# power2pix_connector.net
KiCad netlist of a schematic drawn in Altium Designer
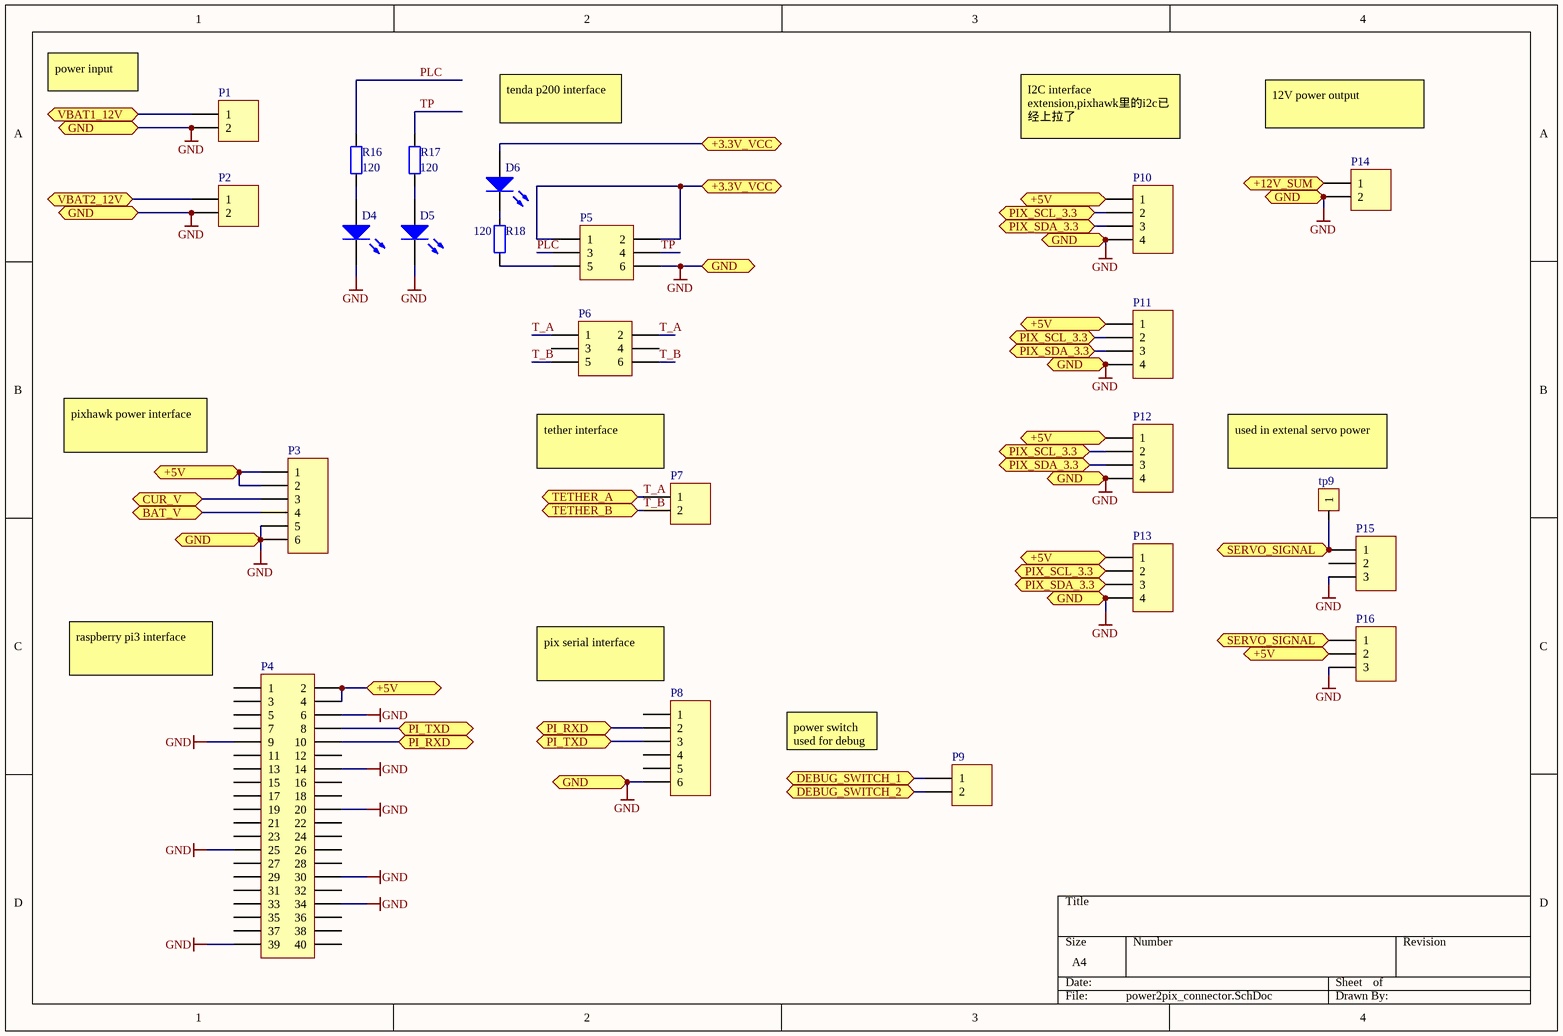
[diagram p0: power2pix_connector.SchDoc]

(export (version "E")
  (design (tool "Eeschema 10.0.6"))
  (components
    (comp (ref "D4")
      (value "LED0")
      (footprint "6-0805_M")
      (description "Typical INFRARED GaAs LED")
      (fields (field (name "PUBLISHER") "Altium Limited"))
      (libsource (lib "Miscellaneous Devices") (part "LED0"))
    )
    (comp (ref "D5")
      (value "LED0")
      (footprint "6-0805_M")
      (description "Typical INFRARED GaAs LED")
      (fields (field (name "PUBLISHER") "Altium Limited"))
      (libsource (lib "Miscellaneous Devices") (part "LED0"))
    )
    (comp (ref "D6")
      (value "LED0")
      (footprint "6-0805_M")
      (description "Typical INFRARED GaAs LED")
      (fields (field (name "PUBLISHER") "Altium Limited"))
      (libsource (lib "Miscellaneous Devices") (part "LED0"))
    )
    (comp (ref "P1")
      (value "Header 2")
      (footprint "M4_POWER")
      (description "Header, 2-Pin")
      (fields (field (name "PUBLISHER") "Altium Limited"))
      (libsource (lib "Miscellaneous Connectors") (part "Header 2"))
    )
    (comp (ref "P2")
      (value "Header 2")
      (footprint "M4_POWER")
      (description "Header, 2-Pin")
      (fields (field (name "PUBLISHER") "Altium Limited"))
      (libsource (lib "Miscellaneous Connectors") (part "Header 2"))
    )
    (comp (ref "P3")
      (value "Header 6")
      (footprint "1.25_6PIN")
      (description "Header, 6-Pin")
      (fields (field (name "PUBLISHER") "Altium Limited"))
      (libsource (lib "Miscellaneous Connectors") (part "Header 6"))
    )
    (comp (ref "P4")
      (value "Header 20X2")
      (footprint "HDR2X20")
      (description "Header, 20-Pin, Dual row")
      (fields (field (name "PUBLISHER") "Altium Limited"))
      (libsource (lib "Miscellaneous Connectors") (part "Header 20X2"))
    )
    (comp (ref "P5")
      (value "Header 3X2")
      (footprint "HDR2X3")
      (description "Header, 3-Pin, Dual row")
      (fields (field (name "PUBLISHER") "Altium Limited"))
      (libsource (lib "Miscellaneous Connectors") (part "Header 3X2"))
    )
    (comp (ref "P6")
      (value "Header 3X2")
      (footprint "HDR2X3")
      (description "Header, 3-Pin, Dual row")
      (fields (field (name "PUBLISHER") "Altium Limited"))
      (libsource (lib "Miscellaneous Connectors") (part "Header 3X2"))
    )
    (comp (ref "P7")
      (value "Header 2")
      (footprint "ConnectorBlue")
      (description "Header, 2-Pin")
      (fields (field (name "PUBLISHER") "Altium Limited"))
      (libsource (lib "Miscellaneous Connectors") (part "Header 2"))
    )
    (comp (ref "P8")
      (value "Header 6")
      (footprint "1.25_6PIN")
      (description "Header, 6-Pin")
      (fields (field (name "PUBLISHER") "Altium Limited"))
      (libsource (lib "Miscellaneous Connectors") (part "Header 6"))
    )
    (comp (ref "P9")
      (value "Header 2")
      (footprint "HDR1X2")
      (description "Header, 2-Pin")
      (fields (field (name "PUBLISHER") "Altium Limited"))
      (libsource (lib "Miscellaneous Connectors") (part "Header 2"))
    )
    (comp (ref "P10")
      (value "Header 4")
      (footprint "1_25_4PIN")
      (description "Header, 4-Pin")
      (fields (field (name "PUBLISHER") "Altium Limited"))
      (libsource (lib "Miscellaneous Connectors") (part "Header 4"))
    )
    (comp (ref "P11")
      (value "Header 4")
      (footprint "HDR1X4")
      (description "Header, 4-Pin")
      (fields (field (name "PUBLISHER") "Altium Limited"))
      (libsource (lib "Miscellaneous Connectors") (part "Header 4"))
    )
    (comp (ref "P12")
      (value "Header 4")
      (footprint "HDR1X4")
      (description "Header, 4-Pin")
      (fields (field (name "PUBLISHER") "Altium Limited"))
      (libsource (lib "Miscellaneous Connectors") (part "Header 4"))
    )
    (comp (ref "P13")
      (value "Header 4")
      (footprint "HDR1X4")
      (description "Header, 4-Pin")
      (fields (field (name "PUBLISHER") "Altium Limited"))
      (libsource (lib "Miscellaneous Connectors") (part "Header 4"))
    )
    (comp (ref "P14")
      (value "Header 2")
      (footprint "M4_POWER")
      (description "Header, 2-Pin")
      (fields (field (name "PUBLISHER") "Altium Limited"))
      (libsource (lib "Miscellaneous Connectors") (part "Header 2"))
    )
    (comp (ref "P15")
      (value "Header 3")
      (footprint "HDR1X3")
      (description "Header, 3-Pin")
      (fields (field (name "PUBLISHER") "Altium Limited"))
      (libsource (lib "Miscellaneous Connectors") (part "Header 3"))
    )
    (comp (ref "P16")
      (value "Header 3")
      (footprint "HDR1X3")
      (description "Header, 3-Pin")
      (fields (field (name "PUBLISHER") "Altium Limited"))
      (libsource (lib "Miscellaneous Connectors") (part "Header 3"))
    )
    (comp (ref "R16")
      (value "120")
      (footprint "6-0805_M")
      (description "Resistor")
      (fields (field (name "Comment") "Res2") (field (name "PUBLISHER") "Altium Limited"))
      (libsource (lib "Miscellaneous Devices") (part "Res2"))
    )
    (comp (ref "R17")
      (value "120")
      (footprint "6-0805_M")
      (description "Resistor")
      (fields (field (name "Comment") "Res2") (field (name "PUBLISHER") "Altium Limited"))
      (libsource (lib "Miscellaneous Devices") (part "Res2"))
    )
    (comp (ref "R18")
      (value "120")
      (footprint "6-0805_M")
      (description "Resistor")
      (fields (field (name "Comment") "Res2") (field (name "PUBLISHER") "Altium Limited"))
      (libsource (lib "Miscellaneous Devices") (part "Res2"))
    )
    (comp (ref "tp9") (value "tp") (footprint "testpoint") (libsource (lib "power2pix_sch_lib") (part "tp")))
  )
  (nets
    (net (code "1") (name "/+3.3V_VCC") (class "Default")
      (node (ref "D6") (pin "1") (pinfunction "A_1") (pintype "passive"))
      (node (ref "P5") (pin "1") (pinfunction "1_1") (pintype "passive"))
      (node (ref "P5") (pin "2") (pinfunction "2_2") (pintype "passive"))
    )
    (net (code "2") (name "/+5V") (class "Default")
      (node (ref "P10") (pin "1") (pinfunction "1_1") (pintype "passive"))
      (node (ref "P11") (pin "1") (pinfunction "1_1") (pintype "passive"))
      (node (ref "P12") (pin "1") (pinfunction "1_1") (pintype "passive"))
      (node (ref "P13") (pin "1") (pinfunction "1_1") (pintype "passive"))
      (node (ref "P16") (pin "2") (pinfunction "2_2") (pintype "passive"))
      (node (ref "P3") (pin "1") (pinfunction "1_1") (pintype "passive"))
      (node (ref "P3") (pin "2") (pinfunction "2_2") (pintype "passive"))
      (node (ref "P4") (pin "2") (pinfunction "2_2") (pintype "passive"))
      (node (ref "P4") (pin "4") (pinfunction "4_4") (pintype "passive"))
    )
    (net (code "3") (name "/+12V_SUM") (class "Default")
      (node (ref "P14") (pin "1") (pinfunction "1_1") (pintype "passive"))
    )
    (net (code "4") (name "/BAT_V") (class "Default")
      (node (ref "P3") (pin "4") (pinfunction "4_4") (pintype "passive"))
    )
    (net (code "5") (name "/CUR_V") (class "Default")
      (node (ref "P3") (pin "3") (pinfunction "3_3") (pintype "passive"))
    )
    (net (code "6") (name "/DEBUG_SWITCH_1") (class "Default")
      (node (ref "P9") (pin "1") (pinfunction "1_1") (pintype "passive"))
    )
    (net (code "7") (name "/DEBUG_SWITCH_2") (class "Default")
      (node (ref "P9") (pin "2") (pinfunction "2_2") (pintype "passive"))
    )
    (net (code "8") (name "/PIX_SCL_3.3") (class "Default")
      (node (ref "P10") (pin "2") (pinfunction "2_2") (pintype "passive"))
      (node (ref "P11") (pin "2") (pinfunction "2_2") (pintype "passive"))
      (node (ref "P12") (pin "2") (pinfunction "2_2") (pintype "passive"))
      (node (ref "P13") (pin "2") (pinfunction "2_2") (pintype "passive"))
    )
    (net (code "9") (name "/PIX_SDA_3.3") (class "Default")
      (node (ref "P10") (pin "3") (pinfunction "3_3") (pintype "passive"))
      (node (ref "P11") (pin "3") (pinfunction "3_3") (pintype "passive"))
      (node (ref "P12") (pin "3") (pinfunction "3_3") (pintype "passive"))
      (node (ref "P13") (pin "3") (pinfunction "3_3") (pintype "passive"))
    )
    (net (code "10") (name "/PI_RXD") (class "Default")
      (node (ref "P4") (pin "10") (pinfunction "10_10") (pintype "passive"))
      (node (ref "P8") (pin "2") (pinfunction "2_2") (pintype "passive"))
    )
    (net (code "11") (name "/PI_TXD") (class "Default")
      (node (ref "P4") (pin "8") (pinfunction "8_8") (pintype "passive"))
      (node (ref "P8") (pin "3") (pinfunction "3_3") (pintype "passive"))
    )
    (net (code "12") (name "/PLC") (class "Default")
      (node (ref "P5") (pin "3") (pinfunction "3_3") (pintype "passive"))
      (node (ref "R16") (pin "2") (pinfunction "2_2") (pintype "passive"))
    )
    (net (code "13") (name "/SERVO_SIGNAL") (class "Default")
      (node (ref "P15") (pin "1") (pinfunction "1_1") (pintype "passive"))
      (node (ref "P16") (pin "1") (pinfunction "1_1") (pintype "passive"))
      (node (ref "tp9") (pin "1") (pinfunction "1_1") (pintype "passive"))
    )
    (net (code "14") (name "/TP") (class "Default")
      (node (ref "P5") (pin "4") (pinfunction "4_4") (pintype "passive"))
      (node (ref "R17") (pin "2") (pinfunction "2_2") (pintype "passive"))
    )
    (net (code "15") (name "/T_A") (class "Default")
      (node (ref "P6") (pin "1") (pinfunction "1_1") (pintype "passive"))
      (node (ref "P6") (pin "2") (pinfunction "2_2") (pintype "passive"))
      (node (ref "P7") (pin "1") (pinfunction "1_1") (pintype "passive"))
    )
    (net (code "16") (name "/T_B") (class "Default")
      (node (ref "P6") (pin "5") (pinfunction "5_5") (pintype "passive"))
      (node (ref "P6") (pin "6") (pinfunction "6_6") (pintype "passive"))
      (node (ref "P7") (pin "2") (pinfunction "2_2") (pintype "passive"))
    )
    (net (code "17") (name "/VBAT1_12V") (class "Default")
      (node (ref "P1") (pin "1") (pinfunction "1_1") (pintype "passive"))
    )
    (net (code "18") (name "/VBAT2_12V") (class "Default")
      (node (ref "P2") (pin "1") (pinfunction "1_1") (pintype "passive"))
    )
    (net (code "19") (name "GND") (class "Default")
      (node (ref "D4") (pin "2") (pinfunction "K_2") (pintype "passive"))
      (node (ref "D5") (pin "2") (pinfunction "K_2") (pintype "passive"))
      (node (ref "P1") (pin "2") (pinfunction "2_2") (pintype "passive"))
      (node (ref "P10") (pin "4") (pinfunction "4_4") (pintype "passive"))
      (node (ref "P11") (pin "4") (pinfunction "4_4") (pintype "passive"))
      (node (ref "P12") (pin "4") (pinfunction "4_4") (pintype "passive"))
      (node (ref "P13") (pin "4") (pinfunction "4_4") (pintype "passive"))
      (node (ref "P14") (pin "2") (pinfunction "2_2") (pintype "passive"))
      (node (ref "P15") (pin "3") (pinfunction "3_3") (pintype "passive"))
      (node (ref "P16") (pin "3") (pinfunction "3_3") (pintype "passive"))
      (node (ref "P2") (pin "2") (pinfunction "2_2") (pintype "passive"))
      (node (ref "P3") (pin "5") (pinfunction "5_5") (pintype "passive"))
      (node (ref "P3") (pin "6") (pinfunction "6_6") (pintype "passive"))
      (node (ref "P4") (pin "14") (pinfunction "14_14") (pintype "passive"))
      (node (ref "P4") (pin "20") (pinfunction "20_20") (pintype "passive"))
      (node (ref "P4") (pin "25") (pinfunction "25_25") (pintype "passive"))
      (node (ref "P4") (pin "30") (pinfunction "30_30") (pintype "passive"))
      (node (ref "P4") (pin "34") (pinfunction "34_34") (pintype "passive"))
      (node (ref "P4") (pin "39") (pinfunction "39_39") (pintype "passive"))
      (node (ref "P4") (pin "6") (pinfunction "6_6") (pintype "passive"))
      (node (ref "P4") (pin "9") (pinfunction "9_9") (pintype "passive"))
      (node (ref "P5") (pin "6") (pinfunction "6_6") (pintype "passive"))
      (node (ref "P8") (pin "6") (pinfunction "6_6") (pintype "passive"))
    )
    (net (code "20") (name "Net-(D4-A)") (class "Default")
      (node (ref "D4") (pin "1") (pinfunction "A_1") (pintype "passive"))
      (node (ref "R16") (pin "1") (pinfunction "1_1") (pintype "passive"))
    )
    (net (code "21") (name "Net-(D5-A)") (class "Default")
      (node (ref "D5") (pin "1") (pinfunction "A_1") (pintype "passive"))
      (node (ref "R17") (pin "1") (pinfunction "1_1") (pintype "passive"))
    )
    (net (code "22") (name "Net-(D6-K)") (class "Default")
      (node (ref "D6") (pin "2") (pinfunction "K_2") (pintype "passive"))
      (node (ref "R18") (pin "2") (pinfunction "2_2") (pintype "passive"))
    )
    (net (code "23") (name "Net-(P5-Pad5)") (class "Default")
      (node (ref "P5") (pin "5") (pinfunction "5_5") (pintype "passive"))
      (node (ref "R18") (pin "1") (pinfunction "1_1") (pintype "passive"))
    )
    (net (code "24") (name "unconnected-(P4-Pad1)") (class "Default")
      (node (ref "P4") (pin "1") (pinfunction "1_1") (pintype "passive"))
    )
    (net (code "25") (name "unconnected-(P4-Pad3)") (class "Default")
      (node (ref "P4") (pin "3") (pinfunction "3_3") (pintype "passive"))
    )
    (net (code "26") (name "unconnected-(P4-Pad5)") (class "Default")
      (node (ref "P4") (pin "5") (pinfunction "5_5") (pintype "passive"))
    )
    (net (code "27") (name "unconnected-(P4-Pad7)") (class "Default")
      (node (ref "P4") (pin "7") (pinfunction "7_7") (pintype "passive"))
    )
    (net (code "28") (name "unconnected-(P4-Pad11)") (class "Default")
      (node (ref "P4") (pin "11") (pinfunction "11_11") (pintype "passive"))
    )
    (net (code "29") (name "unconnected-(P4-Pad12)") (class "Default")
      (node (ref "P4") (pin "12") (pinfunction "12_12") (pintype "passive"))
    )
    (net (code "30") (name "unconnected-(P4-Pad13)") (class "Default")
      (node (ref "P4") (pin "13") (pinfunction "13_13") (pintype "passive"))
    )
    (net (code "31") (name "unconnected-(P4-Pad15)") (class "Default")
      (node (ref "P4") (pin "15") (pinfunction "15_15") (pintype "passive"))
    )
    (net (code "32") (name "unconnected-(P4-Pad16)") (class "Default")
      (node (ref "P4") (pin "16") (pinfunction "16_16") (pintype "passive"))
    )
    (net (code "33") (name "unconnected-(P4-Pad17)") (class "Default")
      (node (ref "P4") (pin "17") (pinfunction "17_17") (pintype "passive"))
    )
    (net (code "34") (name "unconnected-(P4-Pad18)") (class "Default")
      (node (ref "P4") (pin "18") (pinfunction "18_18") (pintype "passive"))
    )
    (net (code "35") (name "unconnected-(P4-Pad19)") (class "Default")
      (node (ref "P4") (pin "19") (pinfunction "19_19") (pintype "passive"))
    )
    (net (code "36") (name "unconnected-(P4-Pad21)") (class "Default")
      (node (ref "P4") (pin "21") (pinfunction "21_21") (pintype "passive"))
    )
    (net (code "37") (name "unconnected-(P4-Pad22)") (class "Default")
      (node (ref "P4") (pin "22") (pinfunction "22_22") (pintype "passive"))
    )
    (net (code "38") (name "unconnected-(P4-Pad23)") (class "Default")
      (node (ref "P4") (pin "23") (pinfunction "23_23") (pintype "passive"))
    )
    (net (code "39") (name "unconnected-(P4-Pad24)") (class "Default")
      (node (ref "P4") (pin "24") (pinfunction "24_24") (pintype "passive"))
    )
    (net (code "40") (name "unconnected-(P4-Pad26)") (class "Default")
      (node (ref "P4") (pin "26") (pinfunction "26_26") (pintype "passive"))
    )
    (net (code "41") (name "unconnected-(P4-Pad27)") (class "Default")
      (node (ref "P4") (pin "27") (pinfunction "27_27") (pintype "passive"))
    )
    (net (code "42") (name "unconnected-(P4-Pad28)") (class "Default")
      (node (ref "P4") (pin "28") (pinfunction "28_28") (pintype "passive"))
    )
    (net (code "43") (name "unconnected-(P4-Pad29)") (class "Default")
      (node (ref "P4") (pin "29") (pinfunction "29_29") (pintype "passive"))
    )
    (net (code "44") (name "unconnected-(P4-Pad31)") (class "Default")
      (node (ref "P4") (pin "31") (pinfunction "31_31") (pintype "passive"))
    )
    (net (code "45") (name "unconnected-(P4-Pad32)") (class "Default")
      (node (ref "P4") (pin "32") (pinfunction "32_32") (pintype "passive"))
    )
    (net (code "46") (name "unconnected-(P4-Pad33)") (class "Default")
      (node (ref "P4") (pin "33") (pinfunction "33_33") (pintype "passive"))
    )
    (net (code "47") (name "unconnected-(P4-Pad35)") (class "Default")
      (node (ref "P4") (pin "35") (pinfunction "35_35") (pintype "passive"))
    )
    (net (code "48") (name "unconnected-(P4-Pad36)") (class "Default")
      (node (ref "P4") (pin "36") (pinfunction "36_36") (pintype "passive"))
    )
    (net (code "49") (name "unconnected-(P4-Pad37)") (class "Default")
      (node (ref "P4") (pin "37") (pinfunction "37_37") (pintype "passive"))
    )
    (net (code "50") (name "unconnected-(P4-Pad38)") (class "Default")
      (node (ref "P4") (pin "38") (pinfunction "38_38") (pintype "passive"))
    )
    (net (code "51") (name "unconnected-(P4-Pad40)") (class "Default")
      (node (ref "P4") (pin "40") (pinfunction "40_40") (pintype "passive"))
    )
    (net (code "52") (name "unconnected-(P6-Pad3)") (class "Default")
      (node (ref "P6") (pin "3") (pinfunction "3_3") (pintype "passive"))
    )
    (net (code "53") (name "unconnected-(P6-Pad4)") (class "Default")
      (node (ref "P6") (pin "4") (pinfunction "4_4") (pintype "passive"))
    )
    (net (code "54") (name "unconnected-(P8-Pad1)") (class "Default")
      (node (ref "P8") (pin "1") (pinfunction "1_1") (pintype "passive"))
    )
    (net (code "55") (name "unconnected-(P8-Pad4)") (class "Default")
      (node (ref "P8") (pin "4") (pinfunction "4_4") (pintype "passive"))
    )
    (net (code "56") (name "unconnected-(P8-Pad5)") (class "Default")
      (node (ref "P8") (pin "5") (pinfunction "5_5") (pintype "passive"))
    )
    (net (code "57") (name "unconnected-(P15-Pad2)") (class "Default")
      (node (ref "P15") (pin "2") (pinfunction "2_2") (pintype "passive"))
    )
  )
)
